# s2m.net
KiCad netlist of a schematic drawn in EAGLE
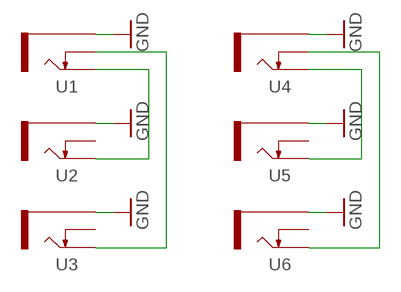
[diagram p0: schematic, sheet 1]

(export (version "E")
  (design (tool "Eeschema 10.0.6"))
  (components
    (comp (ref "U1")
      (value "THONKICONNNEW")
      (footprint "eagle-import:WQP-PJ301M-12_JACK")
      (libsource (lib "eagle-import") (part "THONKICONNNEW"))
    )
    (comp (ref "U2")
      (value "THONKICONNNEW")
      (footprint "eagle-import:WQP-PJ301M-12_JACK")
      (libsource (lib "eagle-import") (part "THONKICONNNEW"))
    )
    (comp (ref "U3")
      (value "THONKICONNNEW")
      (footprint "eagle-import:WQP-PJ301M-12_JACK")
      (libsource (lib "eagle-import") (part "THONKICONNNEW"))
    )
    (comp (ref "U4")
      (value "THONKICONNNEW")
      (footprint "eagle-import:WQP-PJ301M-12_JACK")
      (libsource (lib "eagle-import") (part "THONKICONNNEW"))
    )
    (comp (ref "U5")
      (value "THONKICONNNEW")
      (footprint "eagle-import:WQP-PJ301M-12_JACK")
      (libsource (lib "eagle-import") (part "THONKICONNNEW"))
    )
    (comp (ref "U6")
      (value "THONKICONNNEW")
      (footprint "eagle-import:WQP-PJ301M-12_JACK")
      (libsource (lib "eagle-import") (part "THONKICONNNEW"))
    )
  )
  (nets
    (net (code "1") (name "GND") (class "Default")
      (node (ref "U1") (pin "P$3_SLEEVE") (pinfunction "SLEEVE_P$3_SLEEVE") (pintype "passive"))
      (node (ref "U2") (pin "P$3_SLEEVE") (pinfunction "SLEEVE_P$3_SLEEVE") (pintype "passive"))
      (node (ref "U3") (pin "P$3_SLEEVE") (pinfunction "SLEEVE_P$3_SLEEVE") (pintype "passive"))
      (node (ref "U4") (pin "P$3_SLEEVE") (pinfunction "SLEEVE_P$3_SLEEVE") (pintype "passive"))
      (node (ref "U5") (pin "P$3_SLEEVE") (pinfunction "SLEEVE_P$3_SLEEVE") (pintype "passive"))
      (node (ref "U6") (pin "P$3_SLEEVE") (pinfunction "SLEEVE_P$3_SLEEVE") (pintype "passive"))
    )
    (net (code "2") (name "Net-(U1-SWITCH)") (class "Default")
      (node (ref "U1") (pin "P$2_SWITCH") (pinfunction "SWITCH_P$2_SWITCH") (pintype "passive"))
      (node (ref "U3") (pin "P$1_TIP") (pinfunction "TIP_P$1_TIP") (pintype "passive"))
    )
    (net (code "3") (name "Net-(U1-TIP)") (class "Default")
      (node (ref "U1") (pin "P$1_TIP") (pinfunction "TIP_P$1_TIP") (pintype "passive"))
      (node (ref "U2") (pin "P$1_TIP") (pinfunction "TIP_P$1_TIP") (pintype "passive"))
    )
    (net (code "4") (name "Net-(U4-SWITCH)") (class "Default")
      (node (ref "U4") (pin "P$2_SWITCH") (pinfunction "SWITCH_P$2_SWITCH") (pintype "passive"))
      (node (ref "U6") (pin "P$1_TIP") (pinfunction "TIP_P$1_TIP") (pintype "passive"))
    )
    (net (code "5") (name "Net-(U4-TIP)") (class "Default")
      (node (ref "U4") (pin "P$1_TIP") (pinfunction "TIP_P$1_TIP") (pintype "passive"))
      (node (ref "U5") (pin "P$1_TIP") (pinfunction "TIP_P$1_TIP") (pintype "passive"))
    )
    (net (code "6") (name "unconnected-(U2-SWITCH-PadP$2_SWITCH)") (class "Default")
      (node (ref "U2") (pin "P$2_SWITCH") (pinfunction "SWITCH_P$2_SWITCH") (pintype "passive"))
    )
    (net (code "7") (name "unconnected-(U3-SWITCH-PadP$2_SWITCH)") (class "Default")
      (node (ref "U3") (pin "P$2_SWITCH") (pinfunction "SWITCH_P$2_SWITCH") (pintype "passive"))
    )
    (net (code "8") (name "unconnected-(U5-SWITCH-PadP$2_SWITCH)") (class "Default")
      (node (ref "U5") (pin "P$2_SWITCH") (pinfunction "SWITCH_P$2_SWITCH") (pintype "passive"))
    )
    (net (code "9") (name "unconnected-(U6-SWITCH-PadP$2_SWITCH)") (class "Default")
      (node (ref "U6") (pin "P$2_SWITCH") (pinfunction "SWITCH_P$2_SWITCH") (pintype "passive"))
    )
  )
)
